# Top.net
KiCad netlist of a schematic drawn in Altium Designer
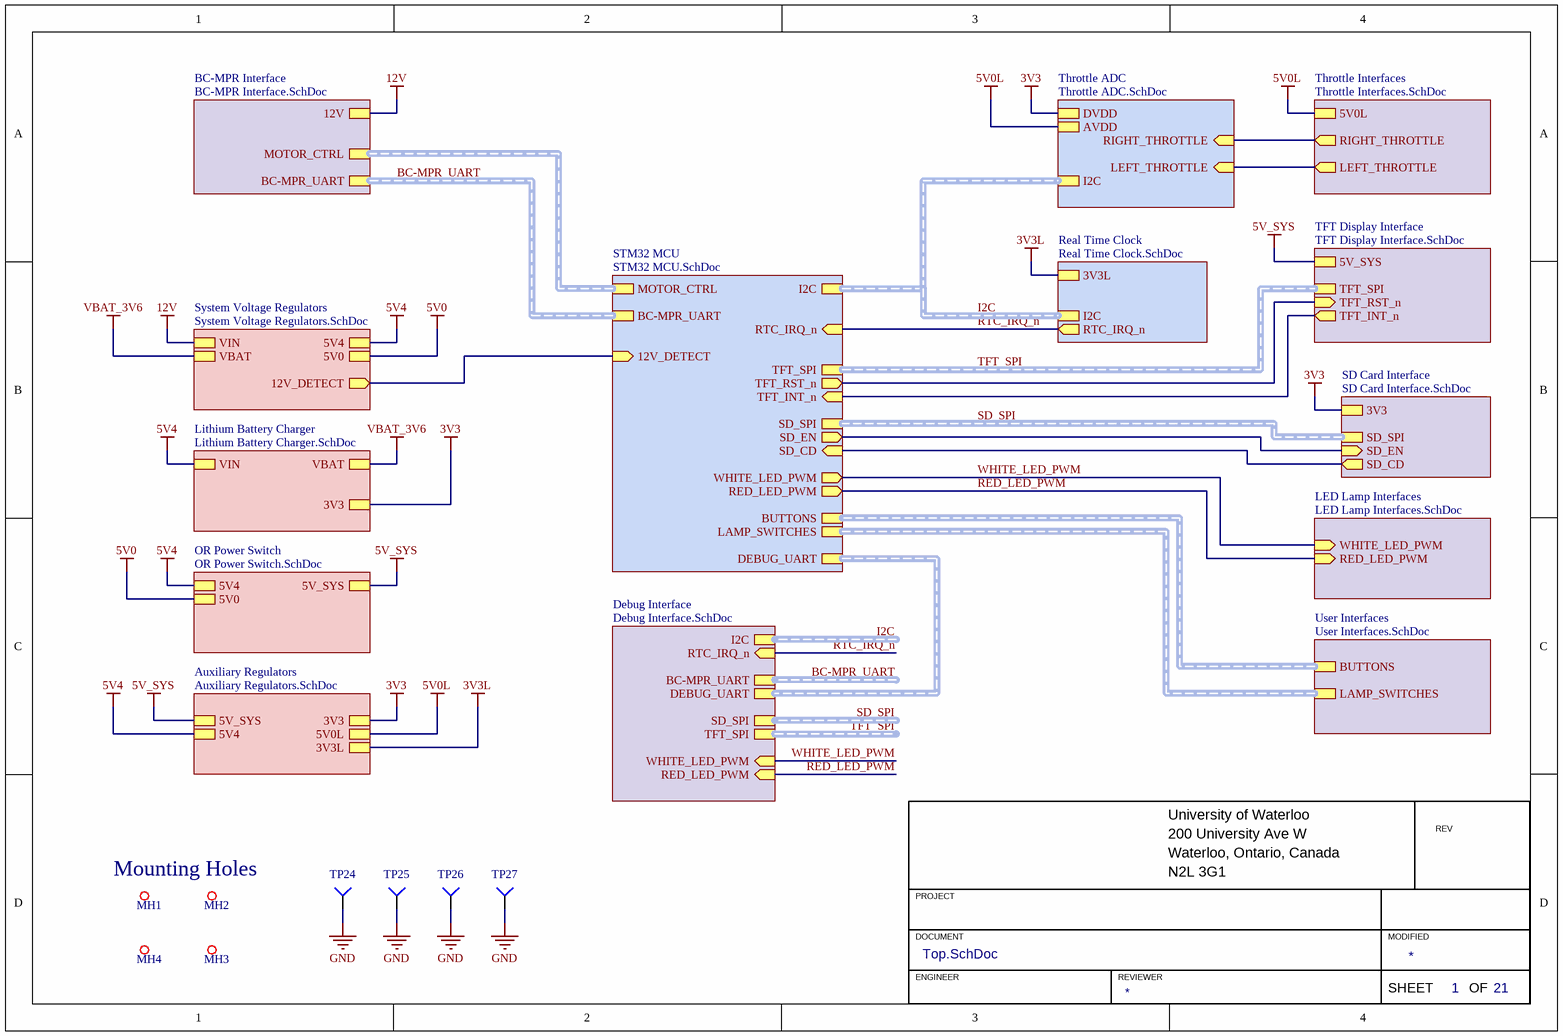
[diagram p0: Top.SchDoc]

(export (version "E")
  (design (tool "Eeschema 10.0.6"))
  (components
    (comp (ref "MH1")
      (value "MOUNTING_HOLE_M3")
      (footprint "MOUNTING_HOLE_3mm")
      (libsource (lib "UWRT_Schematic_Library_2020") (part "MOUNTING_HOLE_M3"))
    )
    (comp (ref "MH2")
      (value "MOUNTING_HOLE_M3")
      (footprint "MOUNTING_HOLE_3mm")
      (libsource (lib "UWRT_Schematic_Library_2020") (part "MOUNTING_HOLE_M3"))
    )
    (comp (ref "MH3")
      (value "MOUNTING_HOLE_M3")
      (footprint "MOUNTING_HOLE_3mm")
      (libsource (lib "UWRT_Schematic_Library_2020") (part "MOUNTING_HOLE_M3"))
    )
    (comp (ref "MH4")
      (value "MOUNTING_HOLE_M3")
      (footprint "MOUNTING_HOLE_3mm")
      (libsource (lib "UWRT_Schematic_Library_2020") (part "MOUNTING_HOLE_M3"))
    )
    (comp (ref "TP24")
      (value "TESTPOINT_KEYSTONE_LOOP")
      (footprint "KEYSTONE_5019")
      (description "PC TEST POINT MINIATURE")
      (libsource (lib "Personal_Schematic_Library_2022") (part "TESTPOINT_KEYSTONE_LOOP"))
    )
    (comp (ref "TP25")
      (value "TESTPOINT_KEYSTONE_LOOP")
      (footprint "KEYSTONE_5019")
      (description "PC TEST POINT MINIATURE")
      (libsource (lib "Personal_Schematic_Library_2022") (part "TESTPOINT_KEYSTONE_LOOP"))
    )
    (comp (ref "TP26")
      (value "TESTPOINT_KEYSTONE_LOOP")
      (footprint "KEYSTONE_5019")
      (description "PC TEST POINT MINIATURE")
      (libsource (lib "Personal_Schematic_Library_2022") (part "TESTPOINT_KEYSTONE_LOOP"))
    )
    (comp (ref "TP27")
      (value "TESTPOINT_KEYSTONE_LOOP")
      (footprint "KEYSTONE_5019")
      (description "PC TEST POINT MINIATURE")
      (libsource (lib "Personal_Schematic_Library_2022") (part "TESTPOINT_KEYSTONE_LOOP"))
    )
  )
  (nets
    (net (code "30") (name "GND") (class "Default")
      (node (ref "TP24") (pin "1") (pinfunction "=value_1") (pintype "passive"))
      (node (ref "TP25") (pin "1") (pinfunction "=value_1") (pintype "passive"))
      (node (ref "TP26") (pin "1") (pinfunction "=value_1") (pintype "passive"))
      (node (ref "TP27") (pin "1") (pinfunction "=value_1") (pintype "passive"))
    )
  )
)
